# dots.net
KiCad netlist of a schematic drawn in EAGLE
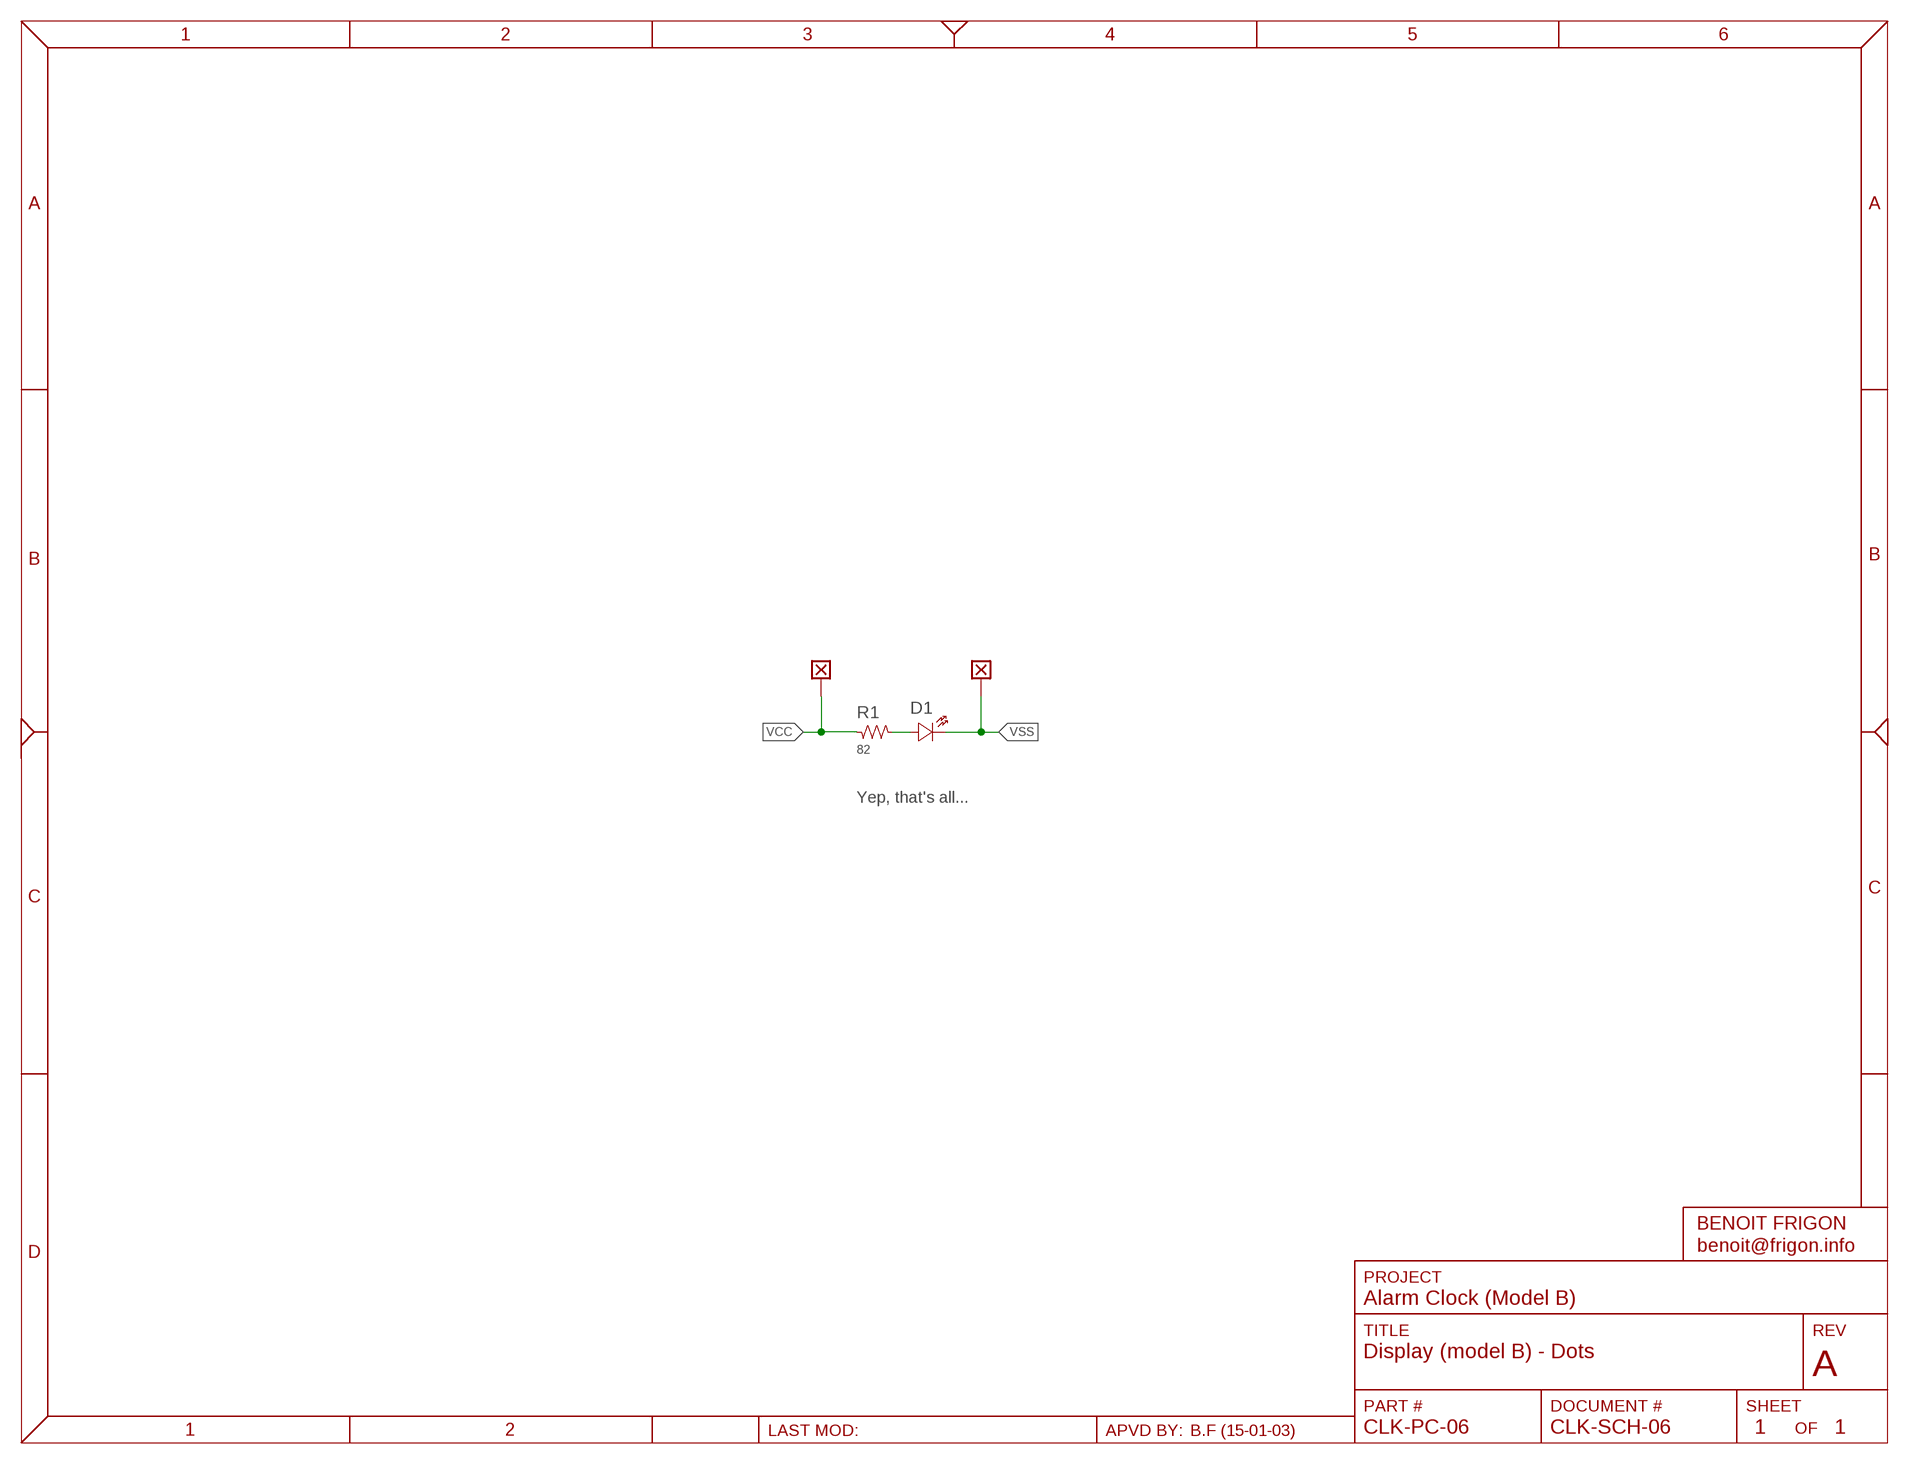
[diagram p0: schematic, sheet 1]

(export (version "E")
  (design (tool "Eeschema 10.0.6"))
  (components
    (comp (ref "D1")
      (value "{ATTR:COLOR}")
      (footprint "eagle-import:CHIPLED_0805")
      (fields (field (name "COLOR") "Orange") (field (name "PART_NO") "APT2012SECK/J4-PRV"))
      (libsource (lib "eagle-import") (part "LED-0805"))
    )
    (comp (ref "R1")
      (value "82")
      (footprint "eagle-import:SMD_0603")
      (libsource (lib "eagle-import") (part "RES-0603"))
    )
    (comp (ref "W1")
      (value "WIRE")
      (footprint "eagle-import:WIRE_SMT")
      (libsource (lib "eagle-import") (part "WIRE"))
    )
    (comp (ref "W2")
      (value "WIRE")
      (footprint "eagle-import:WIRE_SMT")
      (libsource (lib "eagle-import") (part "WIRE"))
    )
  )
  (nets
    (net (code "1") (name "Net-(D1-PadA)") (class "Default")
      (node (ref "D1") (pin "A") (pinfunction "A_A") (pintype "passive"))
      (node (ref "R1") (pin "2") (pinfunction "2_2") (pintype "passive"))
    )
    (net (code "2") (name "VCC") (class "Default")
      (node (ref "R1") (pin "1") (pinfunction "1_1") (pintype "passive"))
      (node (ref "W1") (pin "1") (pinfunction "P$1_1") (pintype "bidirectional"))
    )
    (net (code "3") (name "VSS") (class "Default")
      (node (ref "D1") (pin "K") (pinfunction "K_K") (pintype "passive"))
      (node (ref "W2") (pin "1") (pinfunction "P$1_1") (pintype "bidirectional"))
    )
  )
)
